# vertical_driver.net
KiCad netlist of a schematic drawn in EAGLE
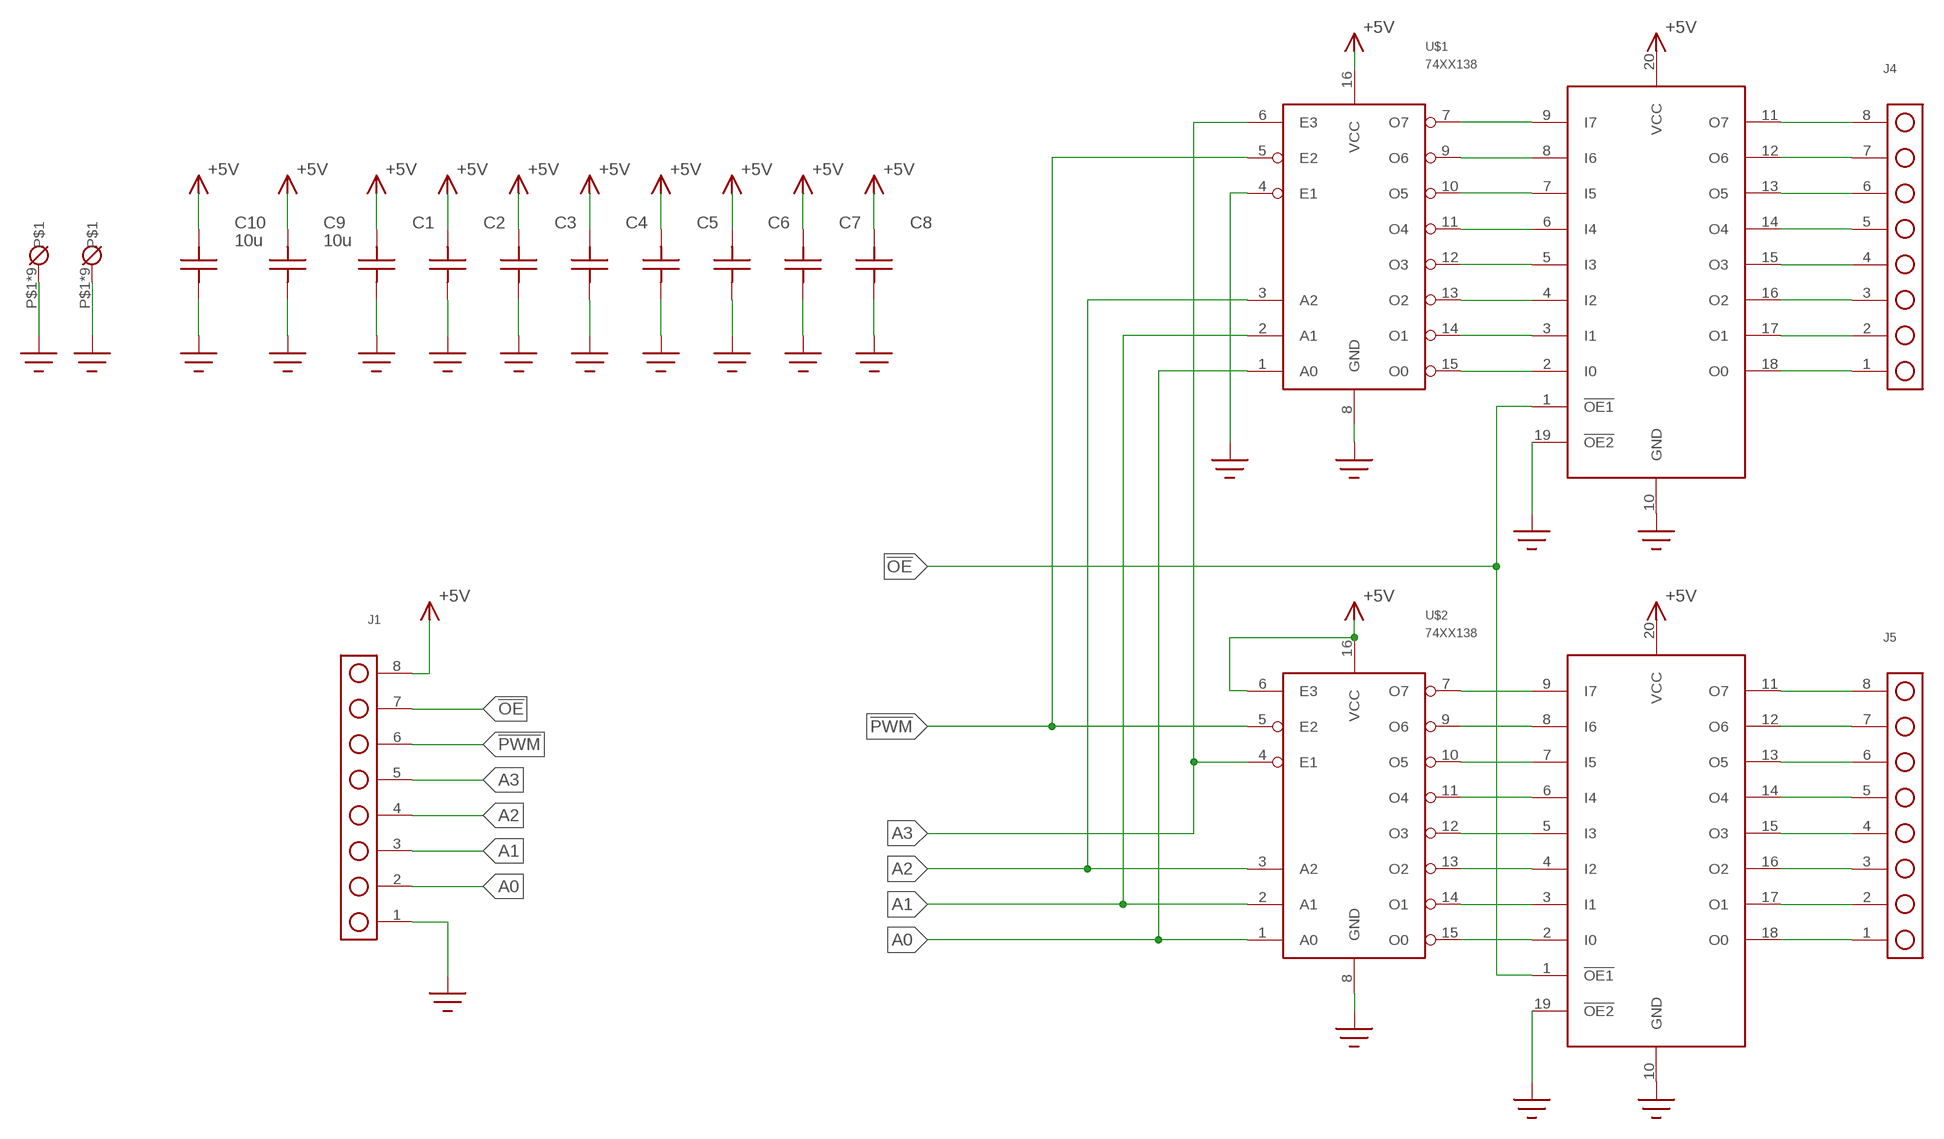
[diagram p0: schematic, sheet 1]

(export (version "E")
  (design (tool "Eeschema 10.0.6"))
  (components
    (comp (ref "C1")
      (value "C0805")
      (footprint "eagle-import:0805")
      (libsource (lib "eagle-import") (part "C0805"))
    )
    (comp (ref "C2")
      (value "C0805")
      (footprint "eagle-import:0805")
      (libsource (lib "eagle-import") (part "C0805"))
    )
    (comp (ref "C3")
      (value "C0805")
      (footprint "eagle-import:0805")
      (libsource (lib "eagle-import") (part "C0805"))
    )
    (comp (ref "C4")
      (value "C0805")
      (footprint "eagle-import:0805")
      (libsource (lib "eagle-import") (part "C0805"))
    )
    (comp (ref "C5")
      (value "C0805")
      (footprint "eagle-import:0805")
      (libsource (lib "eagle-import") (part "C0805"))
    )
    (comp (ref "C6")
      (value "C0805")
      (footprint "eagle-import:0805")
      (libsource (lib "eagle-import") (part "C0805"))
    )
    (comp (ref "C7")
      (value "C0805")
      (footprint "eagle-import:0805")
      (libsource (lib "eagle-import") (part "C0805"))
    )
    (comp (ref "C8")
      (value "C0805")
      (footprint "eagle-import:0805")
      (libsource (lib "eagle-import") (part "C0805"))
    )
    (comp (ref "C9")
      (value "10u")
      (footprint "eagle-import:1206")
      (libsource (lib "eagle-import") (part "C1206"))
    )
    (comp (ref "C10")
      (value "10u")
      (footprint "eagle-import:1206")
      (libsource (lib "eagle-import") (part "C1206"))
    )
    (comp (ref "J1")
      (value "HEADER_8P")
      (footprint "eagle-import:HEADER_8P")
      (libsource (lib "eagle-import") (part "HEADER_8P"))
    )
    (comp (ref "J4")
      (value "HEADER_8P")
      (footprint "eagle-import:HEADER_8P")
      (libsource (lib "eagle-import") (part "HEADER_8P"))
    )
    (comp (ref "J5")
      (value "HEADER_8P")
      (footprint "eagle-import:HEADER_8P")
      (libsource (lib "eagle-import") (part "HEADER_8P"))
    )
    (comp (ref "U$1")
      (value "74XX138")
      (footprint "eagle-import:SOIC-16")
      (libsource (lib "eagle-import") (part "74XX138"))
    )
    (comp (ref "U$2")
      (value "74XX138")
      (footprint "eagle-import:SOIC-16")
      (libsource (lib "eagle-import") (part "74XX138"))
    )
    (comp (ref "U$8")
      (value "74XX540")
      (footprint "eagle-import:SOIC-20W")
      (libsource (lib "eagle-import") (part "74XX540"))
    )
    (comp (ref "U$9")
      (value "74XX540")
      (footprint "eagle-import:SOIC-20W")
      (libsource (lib "eagle-import") (part "74XX540"))
    )
    (comp (ref "U$34")
      (value "MOUNTING_HOLE")
      (footprint "eagle-import:MOUNTING_HOLE_#4")
      (libsource (lib "eagle-import") (part "MOUNTING_HOLE"))
    )
    (comp (ref "U$35")
      (value "MOUNTING_HOLE")
      (footprint "eagle-import:MOUNTING_HOLE_#4")
      (libsource (lib "eagle-import") (part "MOUNTING_HOLE"))
    )
  )
  (nets
    (net (code "1") (name "+5V") (class "Default")
      (node (ref "C1") (pin "P$2") (pinfunction "P$2_P$2") (pintype "bidirectional"))
      (node (ref "C10") (pin "P$2") (pinfunction "P$2_P$2") (pintype "bidirectional"))
      (node (ref "C2") (pin "P$2") (pinfunction "P$2_P$2") (pintype "bidirectional"))
      (node (ref "C3") (pin "P$2") (pinfunction "P$2_P$2") (pintype "bidirectional"))
      (node (ref "C4") (pin "P$2") (pinfunction "P$2_P$2") (pintype "bidirectional"))
      (node (ref "C5") (pin "P$2") (pinfunction "P$2_P$2") (pintype "bidirectional"))
      (node (ref "C6") (pin "P$2") (pinfunction "P$2_P$2") (pintype "bidirectional"))
      (node (ref "C7") (pin "P$2") (pinfunction "P$2_P$2") (pintype "bidirectional"))
      (node (ref "C8") (pin "P$2") (pinfunction "P$2_P$2") (pintype "bidirectional"))
      (node (ref "C9") (pin "P$2") (pinfunction "P$2_P$2") (pintype "bidirectional"))
      (node (ref "J1") (pin "8") (pinfunction "8_8") (pintype "bidirectional"))
      (node (ref "U$1") (pin "16") (pinfunction "VCC_16") (pintype "bidirectional"))
      (node (ref "U$2") (pin "16") (pinfunction "VCC_16") (pintype "bidirectional"))
      (node (ref "U$2") (pin "6") (pinfunction "E3_6") (pintype "bidirectional"))
      (node (ref "U$8") (pin "20") (pinfunction "VCC_20") (pintype "bidirectional"))
      (node (ref "U$9") (pin "20") (pinfunction "VCC_20") (pintype "bidirectional"))
    )
    (net (code "2") (name "/~{OE}") (class "Default")
      (node (ref "J1") (pin "7") (pinfunction "7_7") (pintype "bidirectional"))
      (node (ref "U$8") (pin "1") (pinfunction "~{OE1}_1") (pintype "bidirectional"))
      (node (ref "U$9") (pin "1") (pinfunction "~{OE1}_1") (pintype "bidirectional"))
    )
    (net (code "3") (name "/~{PWM}") (class "Default")
      (node (ref "J1") (pin "6") (pinfunction "6_6") (pintype "bidirectional"))
      (node (ref "U$1") (pin "5") (pinfunction "E2_5") (pintype "bidirectional"))
      (node (ref "U$2") (pin "5") (pinfunction "E2_5") (pintype "bidirectional"))
    )
    (net (code "4") (name "A0") (class "Default")
      (node (ref "J1") (pin "2") (pinfunction "2_2") (pintype "bidirectional"))
      (node (ref "U$1") (pin "1") (pinfunction "A0_1") (pintype "bidirectional"))
      (node (ref "U$2") (pin "1") (pinfunction "A0_1") (pintype "bidirectional"))
    )
    (net (code "5") (name "A1") (class "Default")
      (node (ref "J1") (pin "3") (pinfunction "3_3") (pintype "bidirectional"))
      (node (ref "U$1") (pin "2") (pinfunction "A1_2") (pintype "bidirectional"))
      (node (ref "U$2") (pin "2") (pinfunction "A1_2") (pintype "bidirectional"))
    )
    (net (code "6") (name "A2") (class "Default")
      (node (ref "J1") (pin "4") (pinfunction "4_4") (pintype "bidirectional"))
      (node (ref "U$1") (pin "3") (pinfunction "A2_3") (pintype "bidirectional"))
      (node (ref "U$2") (pin "3") (pinfunction "A2_3") (pintype "bidirectional"))
    )
    (net (code "7") (name "A3") (class "Default")
      (node (ref "J1") (pin "5") (pinfunction "5_5") (pintype "bidirectional"))
      (node (ref "U$1") (pin "6") (pinfunction "E3_6") (pintype "bidirectional"))
      (node (ref "U$2") (pin "4") (pinfunction "E1_4") (pintype "bidirectional"))
    )
    (net (code "8") (name "GND") (class "Default")
      (node (ref "C1") (pin "P$1") (pinfunction "P$1_P$1") (pintype "bidirectional"))
      (node (ref "C10") (pin "P$1") (pinfunction "P$1_P$1") (pintype "bidirectional"))
      (node (ref "C2") (pin "P$1") (pinfunction "P$1_P$1") (pintype "bidirectional"))
      (node (ref "C3") (pin "P$1") (pinfunction "P$1_P$1") (pintype "bidirectional"))
      (node (ref "C4") (pin "P$1") (pinfunction "P$1_P$1") (pintype "bidirectional"))
      (node (ref "C5") (pin "P$1") (pinfunction "P$1_P$1") (pintype "bidirectional"))
      (node (ref "C6") (pin "P$1") (pinfunction "P$1_P$1") (pintype "bidirectional"))
      (node (ref "C7") (pin "P$1") (pinfunction "P$1_P$1") (pintype "bidirectional"))
      (node (ref "C8") (pin "P$1") (pinfunction "P$1_P$1") (pintype "bidirectional"))
      (node (ref "C9") (pin "P$1") (pinfunction "P$1_P$1") (pintype "bidirectional"))
      (node (ref "J1") (pin "1") (pinfunction "1_1") (pintype "bidirectional"))
      (node (ref "U$1") (pin "4") (pinfunction "E1_4") (pintype "bidirectional"))
      (node (ref "U$1") (pin "8") (pinfunction "GND_8") (pintype "bidirectional"))
      (node (ref "U$2") (pin "8") (pinfunction "GND_8") (pintype "bidirectional"))
      (node (ref "U$34") (pin "P$1") (pinfunction "P$1_P$1") (pintype "bidirectional"))
      (node (ref "U$34") (pin "P$2") (pinfunction "P$1_P$2") (pintype "bidirectional"))
      (node (ref "U$34") (pin "P$3") (pinfunction "P$1_P$3") (pintype "bidirectional"))
      (node (ref "U$34") (pin "P$4") (pinfunction "P$1_P$4") (pintype "bidirectional"))
      (node (ref "U$34") (pin "P$5") (pinfunction "P$1_P$5") (pintype "bidirectional"))
      (node (ref "U$34") (pin "P$6") (pinfunction "P$1_P$6") (pintype "bidirectional"))
      (node (ref "U$34") (pin "P$7") (pinfunction "P$1_P$7") (pintype "bidirectional"))
      (node (ref "U$34") (pin "P$8") (pinfunction "P$1_P$8") (pintype "bidirectional"))
      (node (ref "U$34") (pin "P$9") (pinfunction "P$1_P$9") (pintype "bidirectional"))
      (node (ref "U$35") (pin "P$1") (pinfunction "P$1_P$1") (pintype "bidirectional"))
      (node (ref "U$35") (pin "P$2") (pinfunction "P$1_P$2") (pintype "bidirectional"))
      (node (ref "U$35") (pin "P$3") (pinfunction "P$1_P$3") (pintype "bidirectional"))
      (node (ref "U$35") (pin "P$4") (pinfunction "P$1_P$4") (pintype "bidirectional"))
      (node (ref "U$35") (pin "P$5") (pinfunction "P$1_P$5") (pintype "bidirectional"))
      (node (ref "U$35") (pin "P$6") (pinfunction "P$1_P$6") (pintype "bidirectional"))
      (node (ref "U$35") (pin "P$7") (pinfunction "P$1_P$7") (pintype "bidirectional"))
      (node (ref "U$35") (pin "P$8") (pinfunction "P$1_P$8") (pintype "bidirectional"))
      (node (ref "U$35") (pin "P$9") (pinfunction "P$1_P$9") (pintype "bidirectional"))
      (node (ref "U$8") (pin "10") (pinfunction "GND_10") (pintype "bidirectional"))
      (node (ref "U$8") (pin "19") (pinfunction "~{OE2}_19") (pintype "bidirectional"))
      (node (ref "U$9") (pin "10") (pinfunction "GND_10") (pintype "bidirectional"))
      (node (ref "U$9") (pin "19") (pinfunction "~{OE2}_19") (pintype "bidirectional"))
    )
    (net (code "9") (name "Net-(U$1-O0)") (class "Default")
      (node (ref "U$1") (pin "15") (pinfunction "O0_15") (pintype "bidirectional"))
      (node (ref "U$8") (pin "2") (pinfunction "I0_2") (pintype "bidirectional"))
    )
    (net (code "10") (name "Net-(U$1-O1)") (class "Default")
      (node (ref "U$1") (pin "14") (pinfunction "O1_14") (pintype "bidirectional"))
      (node (ref "U$8") (pin "3") (pinfunction "I1_3") (pintype "bidirectional"))
    )
    (net (code "11") (name "Net-(U$1-O2)") (class "Default")
      (node (ref "U$1") (pin "13") (pinfunction "O2_13") (pintype "bidirectional"))
      (node (ref "U$8") (pin "4") (pinfunction "I2_4") (pintype "bidirectional"))
    )
    (net (code "12") (name "Net-(U$1-O3)") (class "Default")
      (node (ref "U$1") (pin "12") (pinfunction "O3_12") (pintype "bidirectional"))
      (node (ref "U$8") (pin "5") (pinfunction "I3_5") (pintype "bidirectional"))
    )
    (net (code "13") (name "Net-(U$1-O4)") (class "Default")
      (node (ref "U$1") (pin "11") (pinfunction "O4_11") (pintype "bidirectional"))
      (node (ref "U$8") (pin "6") (pinfunction "I4_6") (pintype "bidirectional"))
    )
    (net (code "14") (name "Net-(U$1-O5)") (class "Default")
      (node (ref "U$1") (pin "10") (pinfunction "O5_10") (pintype "bidirectional"))
      (node (ref "U$8") (pin "7") (pinfunction "I5_7") (pintype "bidirectional"))
    )
    (net (code "15") (name "Net-(U$1-O6)") (class "Default")
      (node (ref "U$1") (pin "9") (pinfunction "O6_9") (pintype "bidirectional"))
      (node (ref "U$8") (pin "8") (pinfunction "I6_8") (pintype "bidirectional"))
    )
    (net (code "16") (name "Net-(U$1-O7)") (class "Default")
      (node (ref "U$1") (pin "7") (pinfunction "O7_7") (pintype "bidirectional"))
      (node (ref "U$8") (pin "9") (pinfunction "I7_9") (pintype "bidirectional"))
    )
    (net (code "17") (name "Net-(U$2-O0)") (class "Default")
      (node (ref "U$2") (pin "15") (pinfunction "O0_15") (pintype "bidirectional"))
      (node (ref "U$9") (pin "2") (pinfunction "I0_2") (pintype "bidirectional"))
    )
    (net (code "18") (name "Net-(U$2-O1)") (class "Default")
      (node (ref "U$2") (pin "14") (pinfunction "O1_14") (pintype "bidirectional"))
      (node (ref "U$9") (pin "3") (pinfunction "I1_3") (pintype "bidirectional"))
    )
    (net (code "19") (name "Net-(U$2-O2)") (class "Default")
      (node (ref "U$2") (pin "13") (pinfunction "O2_13") (pintype "bidirectional"))
      (node (ref "U$9") (pin "4") (pinfunction "I2_4") (pintype "bidirectional"))
    )
    (net (code "20") (name "Net-(U$2-O3)") (class "Default")
      (node (ref "U$2") (pin "12") (pinfunction "O3_12") (pintype "bidirectional"))
      (node (ref "U$9") (pin "5") (pinfunction "I3_5") (pintype "bidirectional"))
    )
    (net (code "21") (name "Net-(U$2-O4)") (class "Default")
      (node (ref "U$2") (pin "11") (pinfunction "O4_11") (pintype "bidirectional"))
      (node (ref "U$9") (pin "6") (pinfunction "I4_6") (pintype "bidirectional"))
    )
    (net (code "22") (name "Net-(U$2-O5)") (class "Default")
      (node (ref "U$2") (pin "10") (pinfunction "O5_10") (pintype "bidirectional"))
      (node (ref "U$9") (pin "7") (pinfunction "I5_7") (pintype "bidirectional"))
    )
    (net (code "23") (name "Net-(U$2-O6)") (class "Default")
      (node (ref "U$2") (pin "9") (pinfunction "O6_9") (pintype "bidirectional"))
      (node (ref "U$9") (pin "8") (pinfunction "I6_8") (pintype "bidirectional"))
    )
    (net (code "24") (name "Net-(U$2-O7)") (class "Default")
      (node (ref "U$2") (pin "7") (pinfunction "O7_7") (pintype "bidirectional"))
      (node (ref "U$9") (pin "9") (pinfunction "I7_9") (pintype "bidirectional"))
    )
    (net (code "25") (name "Net-(U$8-O0)") (class "Default")
      (node (ref "J4") (pin "1") (pinfunction "1_1") (pintype "bidirectional"))
      (node (ref "U$8") (pin "18") (pinfunction "O0_18") (pintype "bidirectional"))
    )
    (net (code "26") (name "Net-(U$8-O1)") (class "Default")
      (node (ref "J4") (pin "2") (pinfunction "2_2") (pintype "bidirectional"))
      (node (ref "U$8") (pin "17") (pinfunction "O1_17") (pintype "bidirectional"))
    )
    (net (code "27") (name "Net-(U$8-O2)") (class "Default")
      (node (ref "J4") (pin "3") (pinfunction "3_3") (pintype "bidirectional"))
      (node (ref "U$8") (pin "16") (pinfunction "O2_16") (pintype "bidirectional"))
    )
    (net (code "28") (name "Net-(U$8-O3)") (class "Default")
      (node (ref "J4") (pin "4") (pinfunction "4_4") (pintype "bidirectional"))
      (node (ref "U$8") (pin "15") (pinfunction "O3_15") (pintype "bidirectional"))
    )
    (net (code "29") (name "Net-(U$8-O4)") (class "Default")
      (node (ref "J4") (pin "5") (pinfunction "5_5") (pintype "bidirectional"))
      (node (ref "U$8") (pin "14") (pinfunction "O4_14") (pintype "bidirectional"))
    )
    (net (code "30") (name "Net-(U$8-O5)") (class "Default")
      (node (ref "J4") (pin "6") (pinfunction "6_6") (pintype "bidirectional"))
      (node (ref "U$8") (pin "13") (pinfunction "O5_13") (pintype "bidirectional"))
    )
    (net (code "31") (name "Net-(U$8-O6)") (class "Default")
      (node (ref "J4") (pin "7") (pinfunction "7_7") (pintype "bidirectional"))
      (node (ref "U$8") (pin "12") (pinfunction "O6_12") (pintype "bidirectional"))
    )
    (net (code "32") (name "Net-(U$8-O7)") (class "Default")
      (node (ref "J4") (pin "8") (pinfunction "8_8") (pintype "bidirectional"))
      (node (ref "U$8") (pin "11") (pinfunction "O7_11") (pintype "bidirectional"))
    )
    (net (code "33") (name "Net-(U$9-O0)") (class "Default")
      (node (ref "J5") (pin "1") (pinfunction "1_1") (pintype "bidirectional"))
      (node (ref "U$9") (pin "18") (pinfunction "O0_18") (pintype "bidirectional"))
    )
    (net (code "34") (name "Net-(U$9-O1)") (class "Default")
      (node (ref "J5") (pin "2") (pinfunction "2_2") (pintype "bidirectional"))
      (node (ref "U$9") (pin "17") (pinfunction "O1_17") (pintype "bidirectional"))
    )
    (net (code "35") (name "Net-(U$9-O2)") (class "Default")
      (node (ref "J5") (pin "3") (pinfunction "3_3") (pintype "bidirectional"))
      (node (ref "U$9") (pin "16") (pinfunction "O2_16") (pintype "bidirectional"))
    )
    (net (code "36") (name "Net-(U$9-O3)") (class "Default")
      (node (ref "J5") (pin "4") (pinfunction "4_4") (pintype "bidirectional"))
      (node (ref "U$9") (pin "15") (pinfunction "O3_15") (pintype "bidirectional"))
    )
    (net (code "37") (name "Net-(U$9-O4)") (class "Default")
      (node (ref "J5") (pin "5") (pinfunction "5_5") (pintype "bidirectional"))
      (node (ref "U$9") (pin "14") (pinfunction "O4_14") (pintype "bidirectional"))
    )
    (net (code "38") (name "Net-(U$9-O5)") (class "Default")
      (node (ref "J5") (pin "6") (pinfunction "6_6") (pintype "bidirectional"))
      (node (ref "U$9") (pin "13") (pinfunction "O5_13") (pintype "bidirectional"))
    )
    (net (code "39") (name "Net-(U$9-O6)") (class "Default")
      (node (ref "J5") (pin "7") (pinfunction "7_7") (pintype "bidirectional"))
      (node (ref "U$9") (pin "12") (pinfunction "O6_12") (pintype "bidirectional"))
    )
    (net (code "40") (name "Net-(U$9-O7)") (class "Default")
      (node (ref "J5") (pin "8") (pinfunction "8_8") (pintype "bidirectional"))
      (node (ref "U$9") (pin "11") (pinfunction "O7_11") (pintype "bidirectional"))
    )
  )
)
